# ACDC.net
KiCad netlist of a schematic drawn in EAGLE
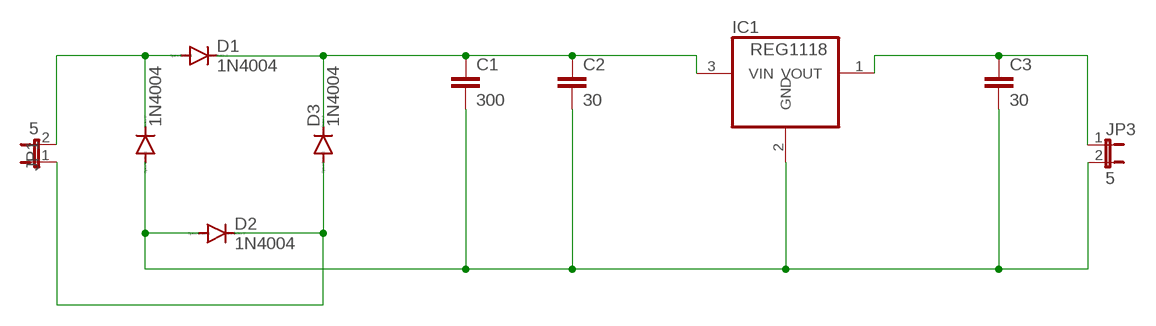
[diagram p0: schematic, sheet 1]

(export (version "E")
  (design (tool "Eeschema 10.0.6"))
  (components
    (comp (ref "C1")
      (value "300")
      (footprint "eagle-import:C2.5-3")
      (libsource (lib "eagle-import") (part "C2,5-3"))
    )
    (comp (ref "C2")
      (value "30")
      (footprint "eagle-import:C2.5-3")
      (libsource (lib "eagle-import") (part "C2,5-3"))
    )
    (comp (ref "C3")
      (value "30")
      (footprint "eagle-import:C2.5-3")
      (libsource (lib "eagle-import") (part "C2,5-3"))
    )
    (comp (ref "D1")
      (value "1N4004")
      (footprint "eagle-import:DO41-10")
      (libsource (lib "eagle-import") (part "1N4004"))
    )
    (comp (ref "D2")
      (value "1N4004")
      (footprint "eagle-import:DO41-10")
      (libsource (lib "eagle-import") (part "1N4004"))
    )
    (comp (ref "D3")
      (value "1N4004")
      (footprint "eagle-import:DO41-10")
      (libsource (lib "eagle-import") (part "1N4004"))
    )
    (comp (ref "D4")
      (value "1N4004")
      (footprint "eagle-import:DO41-10")
      (libsource (lib "eagle-import") (part "1N4004"))
    )
    (comp (ref "IC1")
      (value "REG1118")
      (footprint "eagle-import:SOT223")
      (fields (field (name "MPN") "REG1118-2.85/2K5G4"))
      (libsource (lib "eagle-import") (part "REG1118"))
    )
    (comp (ref "JP1")
      (value "5")
      (footprint "eagle-import:JP1")
      (libsource (lib "eagle-import") (part "JP1E"))
    )
    (comp (ref "JP3")
      (value "5")
      (footprint "eagle-import:JP1")
      (libsource (lib "eagle-import") (part "JP1E"))
    )
  )
  (nets
    (net (code "1") (name "Net-(D1-PadA)") (class "Default")
      (node (ref "D1") (pin "A") (pinfunction "A_A") (pintype "passive"))
      (node (ref "D4") (pin "C") (pinfunction "C_C") (pintype "passive"))
      (node (ref "JP1") (pin "2") (pinfunction "2_2") (pintype "passive"))
    )
    (net (code "2") (name "Net-(D2-PadC)") (class "Default")
      (node (ref "D2") (pin "C") (pinfunction "C_C") (pintype "passive"))
      (node (ref "D3") (pin "A") (pinfunction "A_A") (pintype "passive"))
      (node (ref "JP1") (pin "1") (pinfunction "1_1") (pintype "passive"))
    )
    (net (code "3") (name "Net-(IC1-GND)") (class "Default")
      (node (ref "C1") (pin "2") (pinfunction "2_2") (pintype "passive"))
      (node (ref "C2") (pin "2") (pinfunction "2_2") (pintype "passive"))
      (node (ref "C3") (pin "2") (pinfunction "2_2") (pintype "passive"))
      (node (ref "D2") (pin "A") (pinfunction "A_A") (pintype "passive"))
      (node (ref "D4") (pin "A") (pinfunction "A_A") (pintype "passive"))
      (node (ref "IC1") (pin "2") (pinfunction "GND_2") (pintype "power_in"))
      (node (ref "JP3") (pin "2") (pinfunction "2_2") (pintype "passive"))
    )
    (net (code "4") (name "Net-(IC1-VIN)") (class "Default")
      (node (ref "C1") (pin "1") (pinfunction "1_1") (pintype "passive"))
      (node (ref "C2") (pin "1") (pinfunction "1_1") (pintype "passive"))
      (node (ref "D1") (pin "C") (pinfunction "C_C") (pintype "passive"))
      (node (ref "D3") (pin "C") (pinfunction "C_C") (pintype "passive"))
      (node (ref "IC1") (pin "3") (pinfunction "VIN_3") (pintype "input"))
    )
    (net (code "5") (name "Net-(IC1-VOUT)") (class "Default")
      (node (ref "C3") (pin "1") (pinfunction "1_1") (pintype "passive"))
      (node (ref "IC1") (pin "1") (pinfunction "VOUT_1") (pintype "output"))
      (node (ref "JP3") (pin "1") (pinfunction "1_1") (pintype "passive"))
    )
  )
)
